# Adafruit_MPR121Q_QT_Gator_Breakout.net
KiCad netlist of a schematic drawn in EAGLE
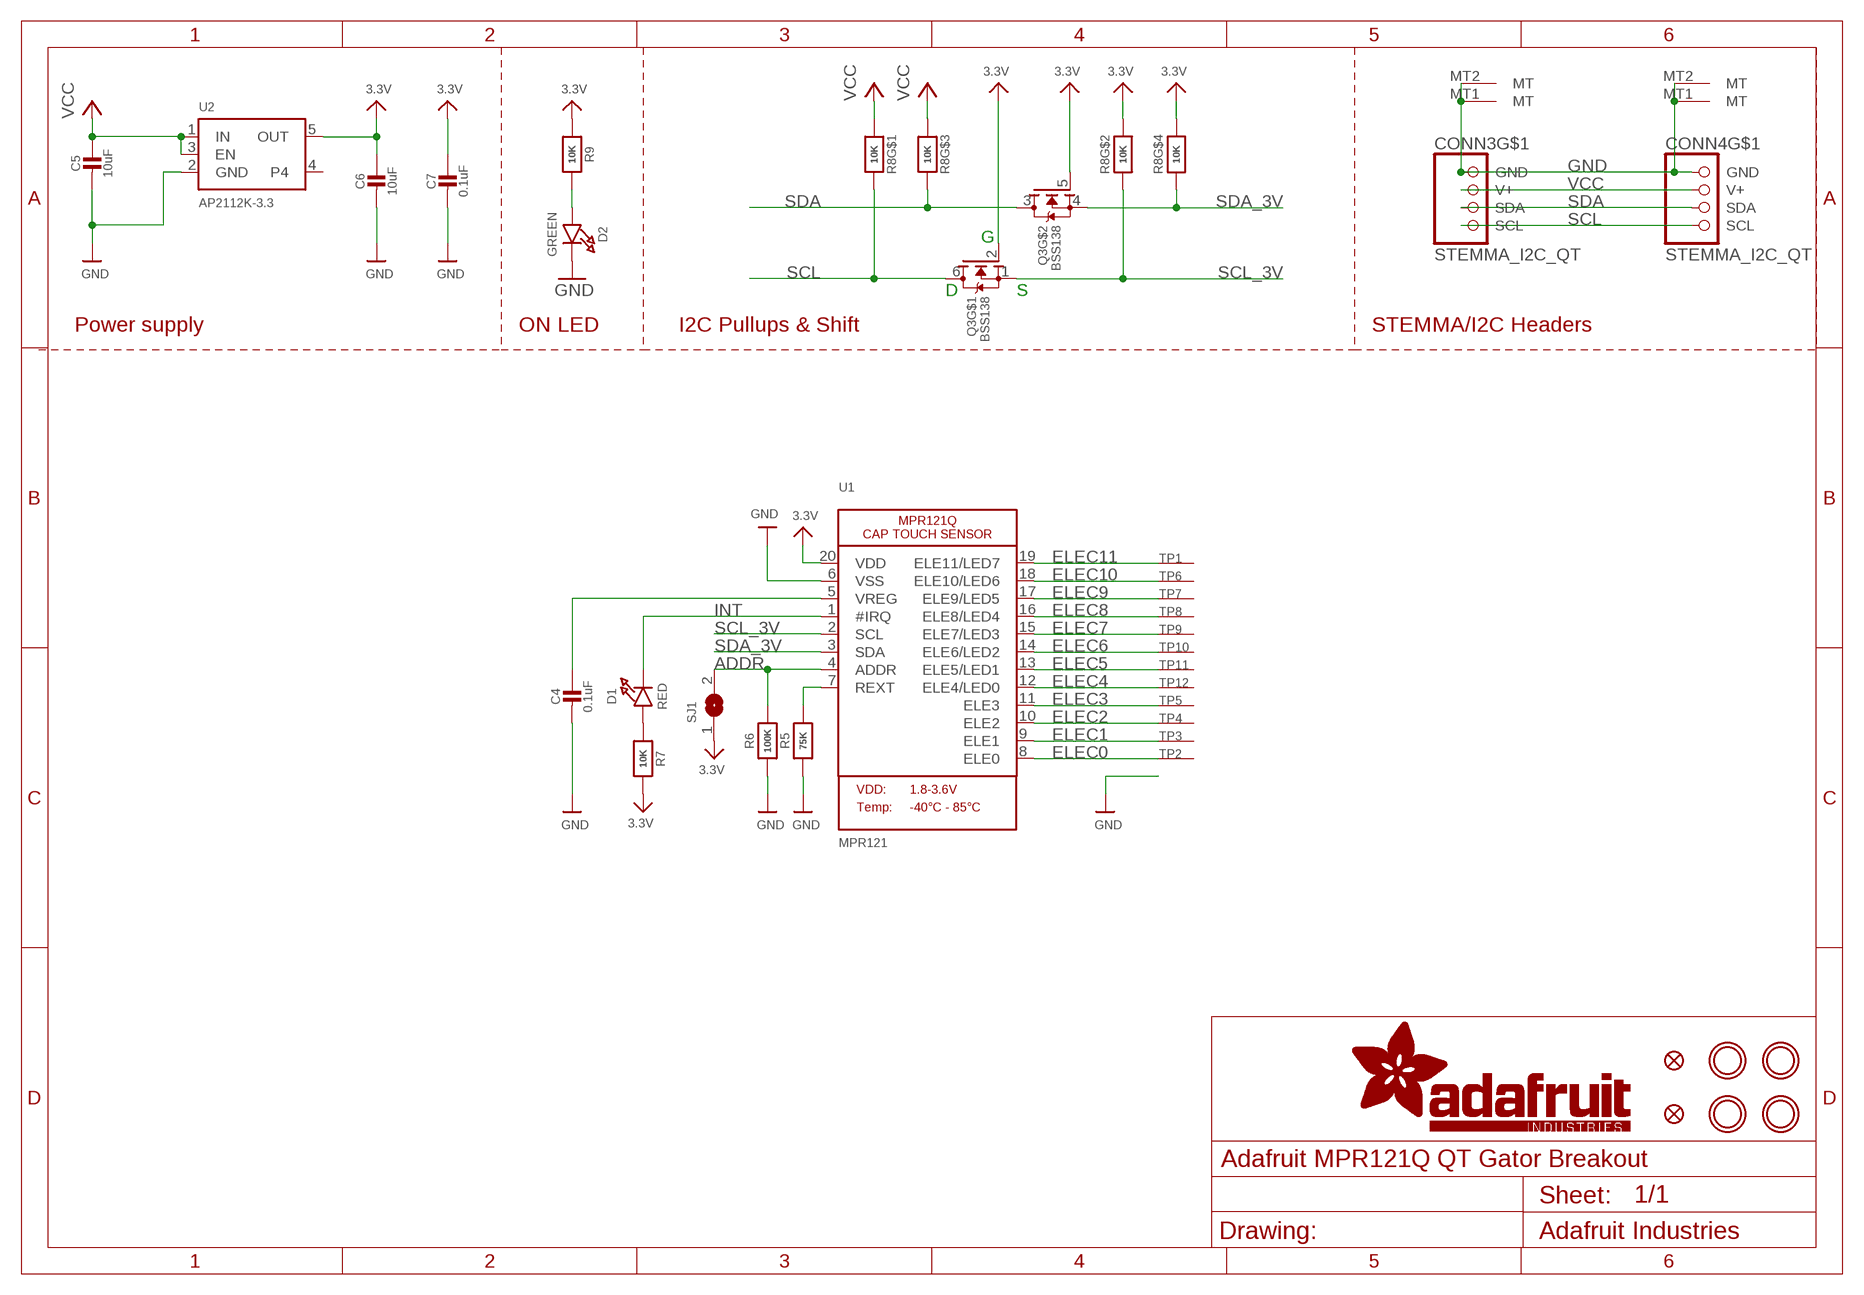
[diagram p0: schematic, sheet 1]

(export (version "E")
  (design (tool "Eeschema 10.0.6"))
  (components
    (comp (ref "C4")
      (value "0.1uF")
      (footprint "eagle-import:0603-NO")
      (libsource (lib "eagle-import") (part "CAP_CERAMIC0603_NO"))
    )
    (comp (ref "C5")
      (value "10uF")
      (footprint "eagle-import:0805-NO")
      (libsource (lib "eagle-import") (part "CAP_CERAMIC0805-NOOUTLINE"))
    )
    (comp (ref "C6")
      (value "10uF")
      (footprint "eagle-import:0805-NO")
      (libsource (lib "eagle-import") (part "CAP_CERAMIC0805-NOOUTLINE"))
    )
    (comp (ref "C7")
      (value "0.1uF")
      (footprint "eagle-import:0603-NO")
      (libsource (lib "eagle-import") (part "CAP_CERAMIC0603_NO"))
    )
    (comp (ref "CONN3")
      (value "STEMMA_I2C_QT")
      (footprint "eagle-import:JST_SH4")
      (libsource (lib "eagle-import") (part "STEMMA_I2C_QT"))
    )
    (comp (ref "CONN4")
      (value "STEMMA_I2C_QT")
      (footprint "eagle-import:JST_SH4")
      (libsource (lib "eagle-import") (part "STEMMA_I2C_QT"))
    )
    (comp (ref "D1")
      (value "RED")
      (footprint "eagle-import:CHIPLED_0603_NOOUTLINE")
      (libsource (lib "eagle-import") (part "LED0603_NOOUTLINE"))
    )
    (comp (ref "D2")
      (value "GREEN")
      (footprint "eagle-import:CHIPLED_0603_NOOUTLINE")
      (libsource (lib "eagle-import") (part "LED0603_NOOUTLINE"))
    )
    (comp (ref "FID3")
      (value "FIDUCIAL_1MM")
      (footprint "eagle-import:FIDUCIAL_1MM")
      (libsource (lib "eagle-import") (part "FIDUCIAL_1MM"))
    )
    (comp (ref "FID4")
      (value "FIDUCIAL_1MM")
      (footprint "eagle-import:FIDUCIAL_1MM")
      (libsource (lib "eagle-import") (part "FIDUCIAL_1MM"))
    )
    (comp (ref "Q3")
      (value "BSS138")
      (footprint "eagle-import:SOT363")
      (libsource (lib "eagle-import") (part "MOSFET-N_DUAL"))
    )
    (comp (ref "R5")
      (value "75K")
      (footprint "eagle-import:0603-NO")
      (libsource (lib "eagle-import") (part "RESISTOR_0603_NOOUT"))
    )
    (comp (ref "R6")
      (value "100K")
      (footprint "eagle-import:0603-NO")
      (libsource (lib "eagle-import") (part "RESISTOR_0603_NOOUT"))
    )
    (comp (ref "R7")
      (value "10K")
      (footprint "eagle-import:0603-NO")
      (fields (field (name "REV") "A"))
      (libsource (lib "eagle-import") (part "RESISTOR_0603_NOOUT"))
    )
    (comp (ref "R8")
      (value "10K")
      (footprint "eagle-import:RESPACK_4X0603")
      (libsource (lib "eagle-import") (part "RESISTOR_4PACK"))
    )
    (comp (ref "R9")
      (value "10K")
      (footprint "eagle-import:0603-NO")
      (libsource (lib "eagle-import") (part "RESISTOR_0603_NOOUT"))
    )
    (comp (ref "SJ1")
      (value "SOLDERJUMPER")
      (footprint "eagle-import:SOLDERJUMPER_ARROW_NOPASTE")
      (libsource (lib "eagle-import") (part "SOLDERJUMPER"))
    )
    (comp (ref "TP1")
      (value "SEWTAPPCB_ALLIGATOR")
      (footprint "eagle-import:PCB_ALLI")
      (libsource (lib "eagle-import") (part "SEWTAPPCB_ALLIGATOR"))
    )
    (comp (ref "TP2")
      (value "SEWTAPPCB_ALLIGATOR")
      (footprint "eagle-import:PCB_ALLI")
      (libsource (lib "eagle-import") (part "SEWTAPPCB_ALLIGATOR"))
    )
    (comp (ref "TP3")
      (value "SEWTAPPCB_ALLIGATOR")
      (footprint "eagle-import:PCB_ALLI")
      (libsource (lib "eagle-import") (part "SEWTAPPCB_ALLIGATOR"))
    )
    (comp (ref "TP4")
      (value "SEWTAPPCB_ALLIGATOR")
      (footprint "eagle-import:PCB_ALLI")
      (libsource (lib "eagle-import") (part "SEWTAPPCB_ALLIGATOR"))
    )
    (comp (ref "TP5")
      (value "SEWTAPPCB_ALLIGATOR")
      (footprint "eagle-import:PCB_ALLI")
      (libsource (lib "eagle-import") (part "SEWTAPPCB_ALLIGATOR"))
    )
    (comp (ref "TP6")
      (value "SEWTAPPCB_ALLIGATOR")
      (footprint "eagle-import:PCB_ALLI")
      (libsource (lib "eagle-import") (part "SEWTAPPCB_ALLIGATOR"))
    )
    (comp (ref "TP7")
      (value "SEWTAPPCB_ALLIGATOR")
      (footprint "eagle-import:PCB_ALLI")
      (libsource (lib "eagle-import") (part "SEWTAPPCB_ALLIGATOR"))
    )
    (comp (ref "TP8")
      (value "SEWTAPPCB_ALLIGATOR")
      (footprint "eagle-import:PCB_ALLI")
      (libsource (lib "eagle-import") (part "SEWTAPPCB_ALLIGATOR"))
    )
    (comp (ref "TP9")
      (value "SEWTAPPCB_ALLIGATOR")
      (footprint "eagle-import:PCB_ALLI")
      (libsource (lib "eagle-import") (part "SEWTAPPCB_ALLIGATOR"))
    )
    (comp (ref "TP10")
      (value "SEWTAPPCB_ALLIGATOR")
      (footprint "eagle-import:PCB_ALLI")
      (libsource (lib "eagle-import") (part "SEWTAPPCB_ALLIGATOR"))
    )
    (comp (ref "TP11")
      (value "SEWTAPPCB_ALLIGATOR")
      (footprint "eagle-import:PCB_ALLI")
      (libsource (lib "eagle-import") (part "SEWTAPPCB_ALLIGATOR"))
    )
    (comp (ref "TP12")
      (value "SEWTAPPCB_ALLIGATOR")
      (footprint "eagle-import:PCB_ALLI")
      (libsource (lib "eagle-import") (part "SEWTAPPCB_ALLIGATOR"))
    )
    (comp (ref "U$7")
      (value "MOUNTINGHOLE2.5")
      (footprint "eagle-import:MOUNTINGHOLE_2.5_PLATED")
      (libsource (lib "eagle-import") (part "MOUNTINGHOLE2.5"))
    )
    (comp (ref "U$8")
      (value "MOUNTINGHOLE2.5")
      (footprint "eagle-import:MOUNTINGHOLE_2.5_PLATED")
      (libsource (lib "eagle-import") (part "MOUNTINGHOLE2.5"))
    )
    (comp (ref "U$34")
      (value "MOUNTINGHOLE2.5")
      (footprint "eagle-import:MOUNTINGHOLE_2.5_PLATED")
      (libsource (lib "eagle-import") (part "MOUNTINGHOLE2.5"))
    )
    (comp (ref "U$35")
      (value "MOUNTINGHOLE2.5")
      (footprint "eagle-import:MOUNTINGHOLE_2.5_PLATED")
      (libsource (lib "eagle-import") (part "MOUNTINGHOLE2.5"))
    )
    (comp (ref "U1")
      (value "MPR121")
      (footprint "eagle-import:QFN20_3MM_NOTHERMAL")
      (libsource (lib "eagle-import") (part "MPR121Q"))
    )
    (comp (ref "U2")
      (value "AP2112K-3.3")
      (footprint "eagle-import:SOT23-5")
      (libsource (lib "eagle-import") (part "VREG_SOT23-5"))
    )
  )
  (nets
    (net (code "1") (name "/ADDR") (class "Default")
      (node (ref "R6") (pin "2") (pinfunction "2_2") (pintype "passive"))
      (node (ref "SJ1") (pin "2") (pinfunction "2_2") (pintype "passive"))
      (node (ref "U1") (pin "4") (pinfunction "ADDR_4") (pintype "bidirectional"))
    )
    (net (code "2") (name "/ELEC0") (class "Default")
      (node (ref "TP2") (pin "P$1") (pinfunction "SEW_P$1") (pintype "bidirectional"))
      (node (ref "U1") (pin "8") (pinfunction "ELE0_8") (pintype "bidirectional"))
    )
    (net (code "3") (name "/ELEC1") (class "Default")
      (node (ref "TP3") (pin "P$1") (pinfunction "SEW_P$1") (pintype "bidirectional"))
      (node (ref "U1") (pin "9") (pinfunction "ELE1_9") (pintype "bidirectional"))
    )
    (net (code "4") (name "/ELEC2") (class "Default")
      (node (ref "TP4") (pin "P$1") (pinfunction "SEW_P$1") (pintype "bidirectional"))
      (node (ref "U1") (pin "10") (pinfunction "ELE2_10") (pintype "bidirectional"))
    )
    (net (code "5") (name "/ELEC3") (class "Default")
      (node (ref "TP5") (pin "P$1") (pinfunction "SEW_P$1") (pintype "bidirectional"))
      (node (ref "U1") (pin "11") (pinfunction "ELE3_11") (pintype "bidirectional"))
    )
    (net (code "6") (name "/ELEC4") (class "Default")
      (node (ref "TP12") (pin "P$1") (pinfunction "SEW_P$1") (pintype "bidirectional"))
      (node (ref "U1") (pin "12") (pinfunction "ELE4/LED0_12") (pintype "bidirectional"))
    )
    (net (code "7") (name "/ELEC5") (class "Default")
      (node (ref "TP11") (pin "P$1") (pinfunction "SEW_P$1") (pintype "bidirectional"))
      (node (ref "U1") (pin "13") (pinfunction "ELE5/LED1_13") (pintype "bidirectional"))
    )
    (net (code "8") (name "/ELEC6") (class "Default")
      (node (ref "TP10") (pin "P$1") (pinfunction "SEW_P$1") (pintype "bidirectional"))
      (node (ref "U1") (pin "14") (pinfunction "ELE6/LED2_14") (pintype "bidirectional"))
    )
    (net (code "9") (name "/ELEC7") (class "Default")
      (node (ref "TP9") (pin "P$1") (pinfunction "SEW_P$1") (pintype "bidirectional"))
      (node (ref "U1") (pin "15") (pinfunction "ELE7/LED3_15") (pintype "bidirectional"))
    )
    (net (code "10") (name "/ELEC8") (class "Default")
      (node (ref "TP8") (pin "P$1") (pinfunction "SEW_P$1") (pintype "bidirectional"))
      (node (ref "U1") (pin "16") (pinfunction "ELE8/LED4_16") (pintype "bidirectional"))
    )
    (net (code "11") (name "/ELEC9") (class "Default")
      (node (ref "TP7") (pin "P$1") (pinfunction "SEW_P$1") (pintype "bidirectional"))
      (node (ref "U1") (pin "17") (pinfunction "ELE9/LED5_17") (pintype "bidirectional"))
    )
    (net (code "12") (name "/ELEC10") (class "Default")
      (node (ref "TP6") (pin "P$1") (pinfunction "SEW_P$1") (pintype "bidirectional"))
      (node (ref "U1") (pin "18") (pinfunction "ELE10/LED6_18") (pintype "bidirectional"))
    )
    (net (code "13") (name "/ELEC11") (class "Default")
      (node (ref "TP1") (pin "P$1") (pinfunction "SEW_P$1") (pintype "bidirectional"))
      (node (ref "U1") (pin "19") (pinfunction "ELE11/LED7_19") (pintype "bidirectional"))
    )
    (net (code "14") (name "/INT") (class "Default")
      (node (ref "D1") (pin "C") (pinfunction "C_C") (pintype "passive"))
      (node (ref "U1") (pin "1") (pinfunction "#IRQ_1") (pintype "bidirectional"))
    )
    (net (code "15") (name "/SCL") (class "Default")
      (node (ref "CONN3") (pin "4") (pinfunction "SCL_4") (pintype "passive"))
      (node (ref "CONN4") (pin "4") (pinfunction "SCL_4") (pintype "passive"))
      (node (ref "Q3") (pin "6") (pinfunction "D_6") (pintype "bidirectional"))
      (node (ref "R8") (pin "8") (pinfunction "2_8") (pintype "passive"))
    )
    (net (code "16") (name "/SCL_3V") (class "Default")
      (node (ref "Q3") (pin "1") (pinfunction "S_1") (pintype "bidirectional"))
      (node (ref "R8") (pin "7") (pinfunction "2_7") (pintype "passive"))
      (node (ref "U1") (pin "2") (pinfunction "SCL_2") (pintype "bidirectional"))
    )
    (net (code "17") (name "/SDA") (class "Default")
      (node (ref "CONN3") (pin "3") (pinfunction "SDA_3") (pintype "passive"))
      (node (ref "CONN4") (pin "3") (pinfunction "SDA_3") (pintype "passive"))
      (node (ref "Q3") (pin "3") (pinfunction "D_3") (pintype "bidirectional"))
      (node (ref "R8") (pin "6") (pinfunction "2_6") (pintype "passive"))
    )
    (net (code "18") (name "/SDA_3V") (class "Default")
      (node (ref "Q3") (pin "4") (pinfunction "S_4") (pintype "bidirectional"))
      (node (ref "R8") (pin "5") (pinfunction "2_5") (pintype "passive"))
      (node (ref "U1") (pin "3") (pinfunction "SDA_3") (pintype "bidirectional"))
    )
    (net (code "19") (name "3.3V") (class "Default")
      (node (ref "C6") (pin "1") (pinfunction "1_1") (pintype "passive"))
      (node (ref "C7") (pin "1") (pinfunction "1_1") (pintype "passive"))
      (node (ref "Q3") (pin "2") (pinfunction "G_2") (pintype "bidirectional"))
      (node (ref "Q3") (pin "5") (pinfunction "G_5") (pintype "bidirectional"))
      (node (ref "R7") (pin "2") (pinfunction "2_2") (pintype "passive"))
      (node (ref "R8") (pin "2") (pinfunction "1_2") (pintype "passive"))
      (node (ref "R8") (pin "4") (pinfunction "1_4") (pintype "passive"))
      (node (ref "R9") (pin "1") (pinfunction "1_1") (pintype "passive"))
      (node (ref "SJ1") (pin "1") (pinfunction "1_1") (pintype "passive"))
      (node (ref "U1") (pin "20") (pinfunction "VDD_20") (pintype "power_in"))
      (node (ref "U2") (pin "5") (pinfunction "OUT_5") (pintype "power_in"))
    )
    (net (code "20") (name "GND") (class "Default")
      (node (ref "C4") (pin "2") (pinfunction "2_2") (pintype "passive"))
      (node (ref "C5") (pin "2") (pinfunction "2_2") (pintype "passive"))
      (node (ref "C6") (pin "2") (pinfunction "2_2") (pintype "passive"))
      (node (ref "C7") (pin "2") (pinfunction "2_2") (pintype "passive"))
      (node (ref "CONN3") (pin "1") (pinfunction "GND_1") (pintype "passive"))
      (node (ref "CONN3") (pin "MT1") (pinfunction "MT_MT1") (pintype "bidirectional"))
      (node (ref "CONN3") (pin "MT2") (pinfunction "MT_MT2") (pintype "bidirectional"))
      (node (ref "CONN4") (pin "1") (pinfunction "GND_1") (pintype "passive"))
      (node (ref "CONN4") (pin "MT1") (pinfunction "MT_MT1") (pintype "bidirectional"))
      (node (ref "CONN4") (pin "MT2") (pinfunction "MT_MT2") (pintype "bidirectional"))
      (node (ref "D2") (pin "C") (pinfunction "C_C") (pintype "passive"))
      (node (ref "R5") (pin "1") (pinfunction "1_1") (pintype "passive"))
      (node (ref "R6") (pin "1") (pinfunction "1_1") (pintype "passive"))
      (node (ref "U1") (pin "6") (pinfunction "VSS_6") (pintype "power_in"))
      (node (ref "U2") (pin "2") (pinfunction "GND_2") (pintype "power_in"))
    )
    (net (code "21") (name "Net-(D1-PadA)") (class "Default")
      (node (ref "D1") (pin "A") (pinfunction "A_A") (pintype "passive"))
      (node (ref "R7") (pin "1") (pinfunction "1_1") (pintype "passive"))
    )
    (net (code "22") (name "Net-(D2-PadA)") (class "Default")
      (node (ref "D2") (pin "A") (pinfunction "A_A") (pintype "passive"))
      (node (ref "R9") (pin "2") (pinfunction "2_2") (pintype "passive"))
    )
    (net (code "23") (name "Net-(U1-REXT)") (class "Default")
      (node (ref "R5") (pin "2") (pinfunction "2_2") (pintype "passive"))
      (node (ref "U1") (pin "7") (pinfunction "REXT_7") (pintype "bidirectional"))
    )
    (net (code "24") (name "Net-(U1-VREG)") (class "Default")
      (node (ref "C4") (pin "1") (pinfunction "1_1") (pintype "passive"))
      (node (ref "U1") (pin "5") (pinfunction "VREG_5") (pintype "bidirectional"))
    )
    (net (code "25") (name "VCC") (class "Default")
      (node (ref "C5") (pin "1") (pinfunction "1_1") (pintype "passive"))
      (node (ref "CONN3") (pin "2") (pinfunction "V+_2") (pintype "passive"))
      (node (ref "CONN4") (pin "2") (pinfunction "V+_2") (pintype "passive"))
      (node (ref "R8") (pin "1") (pinfunction "1_1") (pintype "passive"))
      (node (ref "R8") (pin "3") (pinfunction "1_3") (pintype "passive"))
      (node (ref "U2") (pin "1") (pinfunction "IN_1") (pintype "power_in"))
      (node (ref "U2") (pin "3") (pinfunction "EN_3") (pintype "input"))
    )
    (net (code "26") (name "unconnected-(U2-P4-Pad4)") (class "Default")
      (node (ref "U2") (pin "4") (pinfunction "P4_4") (pintype "bidirectional"))
    )
  )
)
